# M81_1_0.net
KiCad netlist of a schematic drawn in EAGLE
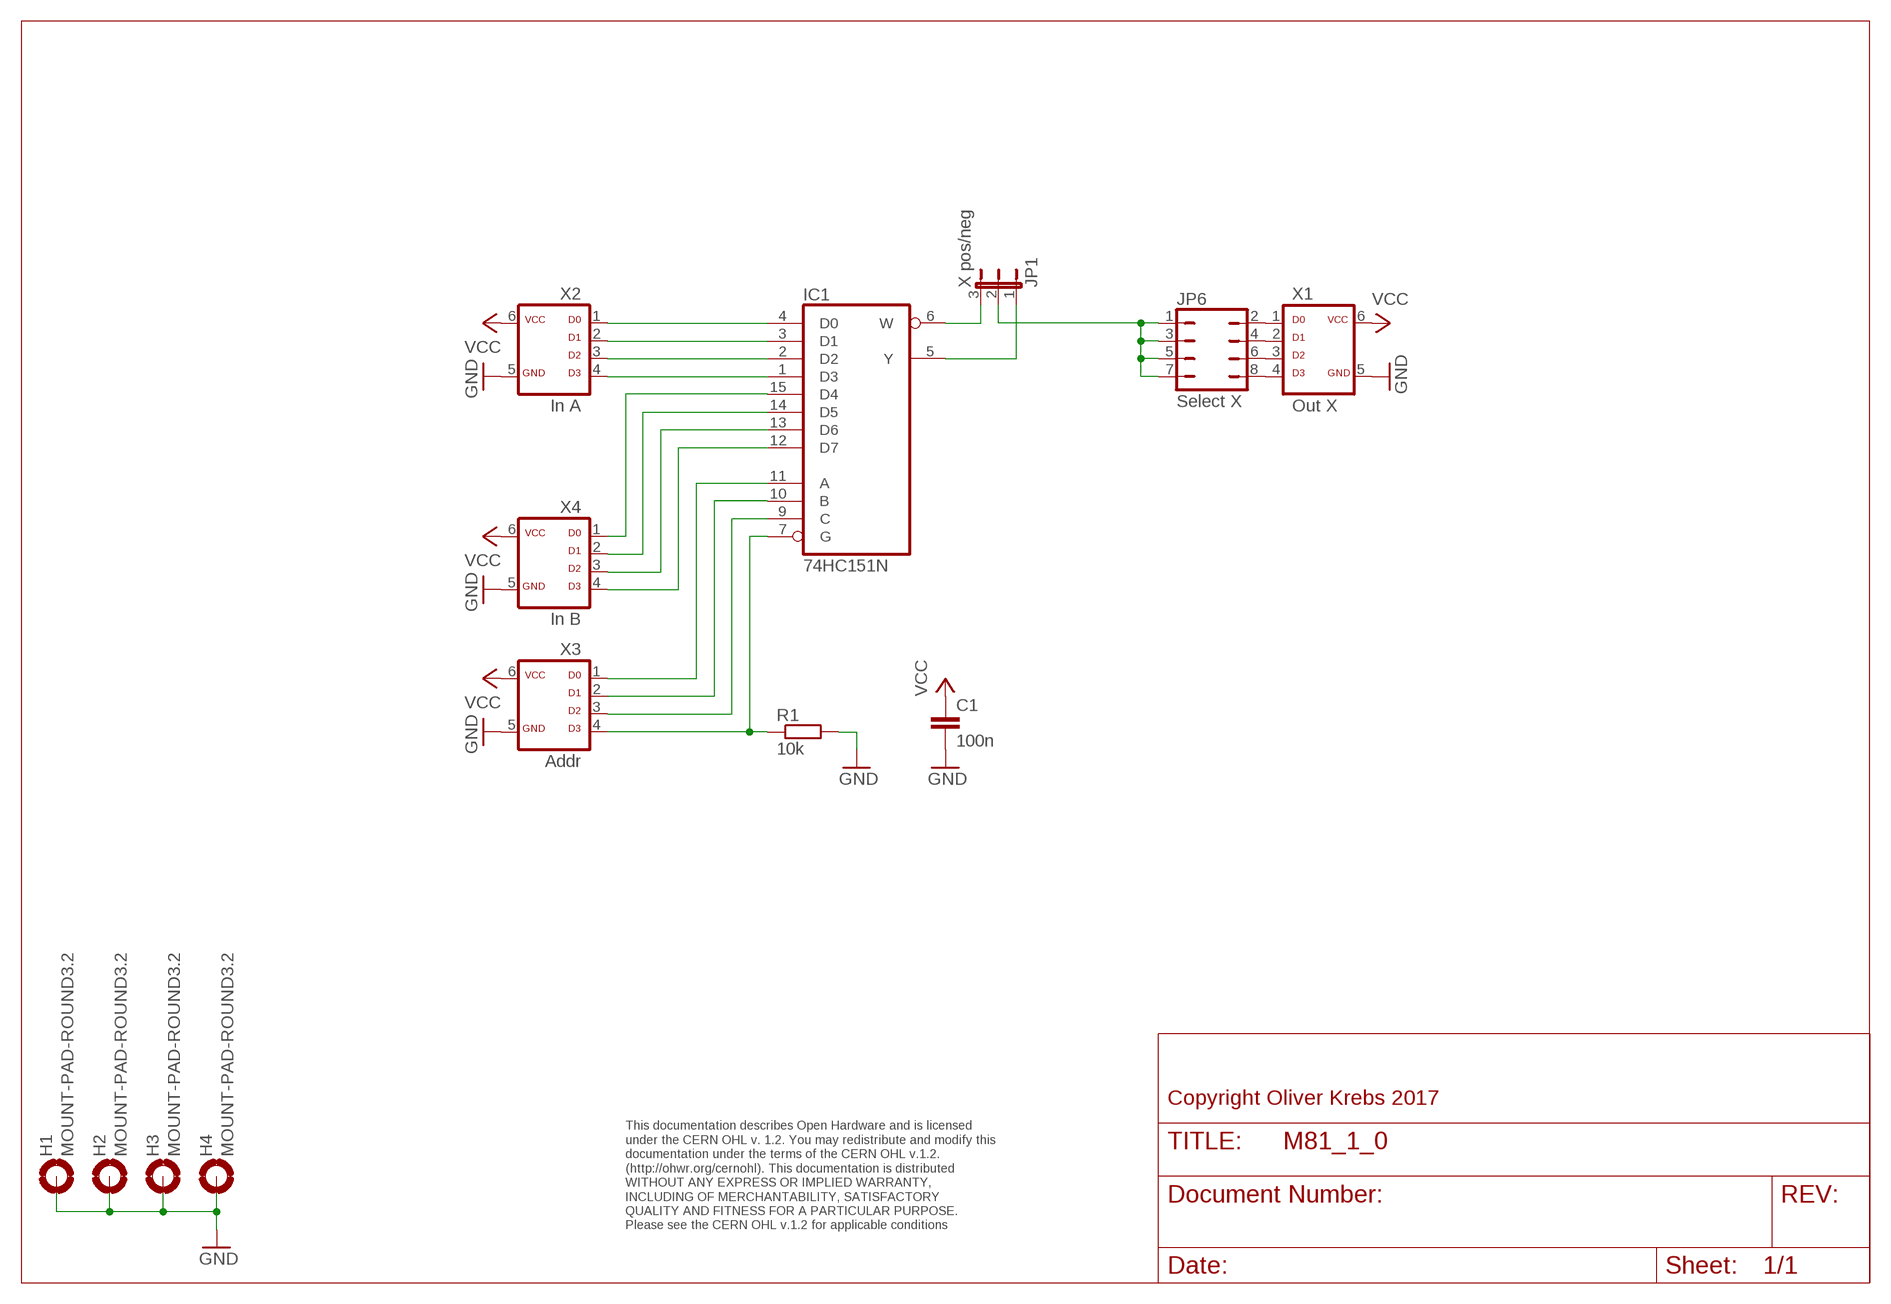
[diagram p0: schematic, sheet 1]

(export (version "E")
  (design (tool "Eeschema 10.0.6"))
  (components
    (comp (ref "C1")
      (value "100n")
      (footprint "eagle-import:C050-025X075")
      (libsource (lib "eagle-import") (part "C-EU050-025X075"))
    )
    (comp (ref "H1")
      (value "MOUNT-PAD-ROUND3.2")
      (footprint "eagle-import:3,2-PAD")
      (libsource (lib "eagle-import") (part "MOUNT-PAD-ROUND3.2"))
    )
    (comp (ref "H2")
      (value "MOUNT-PAD-ROUND3.2")
      (footprint "eagle-import:3,2-PAD")
      (libsource (lib "eagle-import") (part "MOUNT-PAD-ROUND3.2"))
    )
    (comp (ref "H3")
      (value "MOUNT-PAD-ROUND3.2")
      (footprint "eagle-import:3,2-PAD")
      (libsource (lib "eagle-import") (part "MOUNT-PAD-ROUND3.2"))
    )
    (comp (ref "H4")
      (value "MOUNT-PAD-ROUND3.2")
      (footprint "eagle-import:3,2-PAD")
      (libsource (lib "eagle-import") (part "MOUNT-PAD-ROUND3.2"))
    )
    (comp (ref "IC1")
      (value "74HC151N")
      (footprint "eagle-import:DIL16")
      (libsource (lib "eagle-import") (part "74151NHC"))
    )
    (comp (ref "JP1")
      (value "X pos/neg")
      (footprint "eagle-import:JP2")
      (libsource (lib "eagle-import") (part "JP2E"))
    )
    (comp (ref "JP6")
      (value "Select X")
      (footprint "eagle-import:JP4Q")
      (libsource (lib "eagle-import") (part "JP4Q"))
    )
    (comp (ref "R1")
      (value "10k")
      (footprint "eagle-import:0207_10")
      (libsource (lib "eagle-import") (part "R-EU_0207/10"))
    )
    (comp (ref "X1")
      (value "Out X")
      (footprint "eagle-import:ML-6")
      (libsource (lib "eagle-import") (part "ML6D"))
    )
    (comp (ref "X2")
      (value "In A")
      (footprint "eagle-import:ML-6")
      (libsource (lib "eagle-import") (part "ML6D"))
    )
    (comp (ref "X3")
      (value "Addr")
      (footprint "eagle-import:ML-6")
      (libsource (lib "eagle-import") (part "ML6D"))
    )
    (comp (ref "X4")
      (value "In B")
      (footprint "eagle-import:ML-6")
      (libsource (lib "eagle-import") (part "ML6D"))
    )
  )
  (nets
    (net (code "1") (name "GND") (class "Default")
      (node (ref "C1") (pin "2") (pinfunction "2_2") (pintype "passive"))
      (node (ref "H1") (pin "B3,2") (pinfunction "MOUNT_B3,2") (pintype "passive"))
      (node (ref "H2") (pin "B3,2") (pinfunction "MOUNT_B3,2") (pintype "passive"))
      (node (ref "H3") (pin "B3,2") (pinfunction "MOUNT_B3,2") (pintype "passive"))
      (node (ref "H4") (pin "B3,2") (pinfunction "MOUNT_B3,2") (pintype "passive"))
      (node (ref "R1") (pin "2") (pinfunction "2_2") (pintype "passive"))
      (node (ref "X1") (pin "5") (pinfunction "5_5") (pintype "passive"))
      (node (ref "X2") (pin "5") (pinfunction "5_5") (pintype "passive"))
      (node (ref "X3") (pin "5") (pinfunction "5_5") (pintype "passive"))
      (node (ref "X4") (pin "5") (pinfunction "5_5") (pintype "passive"))
    )
    (net (code "2") (name "Net-(IC1A-A)") (class "Default")
      (node (ref "IC1") (pin "11") (pinfunction "A_11") (pintype "input"))
      (node (ref "X3") (pin "1") (pinfunction "1_1") (pintype "passive"))
    )
    (net (code "3") (name "Net-(IC1A-B)") (class "Default")
      (node (ref "IC1") (pin "10") (pinfunction "B_10") (pintype "input"))
      (node (ref "X3") (pin "2") (pinfunction "2_2") (pintype "passive"))
    )
    (net (code "4") (name "Net-(IC1A-C)") (class "Default")
      (node (ref "IC1") (pin "9") (pinfunction "C_9") (pintype "input"))
      (node (ref "X3") (pin "3") (pinfunction "3_3") (pintype "passive"))
    )
    (net (code "5") (name "Net-(IC1A-D0)") (class "Default")
      (node (ref "IC1") (pin "4") (pinfunction "D0_4") (pintype "input"))
      (node (ref "X2") (pin "1") (pinfunction "1_1") (pintype "passive"))
    )
    (net (code "6") (name "Net-(IC1A-D1)") (class "Default")
      (node (ref "IC1") (pin "3") (pinfunction "D1_3") (pintype "input"))
      (node (ref "X2") (pin "2") (pinfunction "2_2") (pintype "passive"))
    )
    (net (code "7") (name "Net-(IC1A-D2)") (class "Default")
      (node (ref "IC1") (pin "2") (pinfunction "D2_2") (pintype "input"))
      (node (ref "X2") (pin "3") (pinfunction "3_3") (pintype "passive"))
    )
    (net (code "8") (name "Net-(IC1A-D3)") (class "Default")
      (node (ref "IC1") (pin "1") (pinfunction "D3_1") (pintype "input"))
      (node (ref "X2") (pin "4") (pinfunction "4_4") (pintype "passive"))
    )
    (net (code "9") (name "Net-(IC1A-D4)") (class "Default")
      (node (ref "IC1") (pin "15") (pinfunction "D4_15") (pintype "input"))
      (node (ref "X4") (pin "1") (pinfunction "1_1") (pintype "passive"))
    )
    (net (code "10") (name "Net-(IC1A-D5)") (class "Default")
      (node (ref "IC1") (pin "14") (pinfunction "D5_14") (pintype "input"))
      (node (ref "X4") (pin "2") (pinfunction "2_2") (pintype "passive"))
    )
    (net (code "11") (name "Net-(IC1A-D6)") (class "Default")
      (node (ref "IC1") (pin "13") (pinfunction "D6_13") (pintype "input"))
      (node (ref "X4") (pin "3") (pinfunction "3_3") (pintype "passive"))
    )
    (net (code "12") (name "Net-(IC1A-D7)") (class "Default")
      (node (ref "IC1") (pin "12") (pinfunction "D7_12") (pintype "input"))
      (node (ref "X4") (pin "4") (pinfunction "4_4") (pintype "passive"))
    )
    (net (code "13") (name "Net-(IC1A-G)") (class "Default")
      (node (ref "IC1") (pin "7") (pinfunction "G_7") (pintype "input"))
      (node (ref "R1") (pin "1") (pinfunction "1_1") (pintype "passive"))
      (node (ref "X3") (pin "4") (pinfunction "4_4") (pintype "passive"))
    )
    (net (code "14") (name "Net-(IC1A-W)") (class "Default")
      (node (ref "IC1") (pin "6") (pinfunction "W_6") (pintype "output"))
      (node (ref "JP1") (pin "3") (pinfunction "3_3") (pintype "passive"))
    )
    (net (code "15") (name "Net-(IC1A-Y)") (class "Default")
      (node (ref "IC1") (pin "5") (pinfunction "Y_5") (pintype "output"))
      (node (ref "JP1") (pin "1") (pinfunction "1_1") (pintype "passive"))
    )
    (net (code "16") (name "Net-(JP1-Pad2)") (class "Default")
      (node (ref "JP1") (pin "2") (pinfunction "2_2") (pintype "passive"))
      (node (ref "JP6") (pin "1") (pinfunction "1_1") (pintype "passive"))
      (node (ref "JP6") (pin "3") (pinfunction "3_3") (pintype "passive"))
      (node (ref "JP6") (pin "5") (pinfunction "5_5") (pintype "passive"))
      (node (ref "JP6") (pin "7") (pinfunction "7_7") (pintype "passive"))
    )
    (net (code "17") (name "Net-(JP6-Pad2)") (class "Default")
      (node (ref "JP6") (pin "2") (pinfunction "2_2") (pintype "passive"))
      (node (ref "X1") (pin "1") (pinfunction "1_1") (pintype "passive"))
    )
    (net (code "18") (name "Net-(JP6-Pad4)") (class "Default")
      (node (ref "JP6") (pin "4") (pinfunction "4_4") (pintype "passive"))
      (node (ref "X1") (pin "2") (pinfunction "2_2") (pintype "passive"))
    )
    (net (code "19") (name "Net-(JP6-Pad6)") (class "Default")
      (node (ref "JP6") (pin "6") (pinfunction "6_6") (pintype "passive"))
      (node (ref "X1") (pin "3") (pinfunction "3_3") (pintype "passive"))
    )
    (net (code "20") (name "Net-(JP6-Pad8)") (class "Default")
      (node (ref "JP6") (pin "8") (pinfunction "8_8") (pintype "passive"))
      (node (ref "X1") (pin "4") (pinfunction "4_4") (pintype "passive"))
    )
    (net (code "21") (name "VCC") (class "Default")
      (node (ref "C1") (pin "1") (pinfunction "1_1") (pintype "passive"))
      (node (ref "X1") (pin "6") (pinfunction "6_6") (pintype "passive"))
      (node (ref "X2") (pin "6") (pinfunction "6_6") (pintype "passive"))
      (node (ref "X3") (pin "6") (pinfunction "6_6") (pintype "passive"))
      (node (ref "X4") (pin "6") (pinfunction "6_6") (pintype "passive"))
    )
  )
)
